# adc_AD7714.net
KiCad netlist of a schematic drawn in Altium Designer
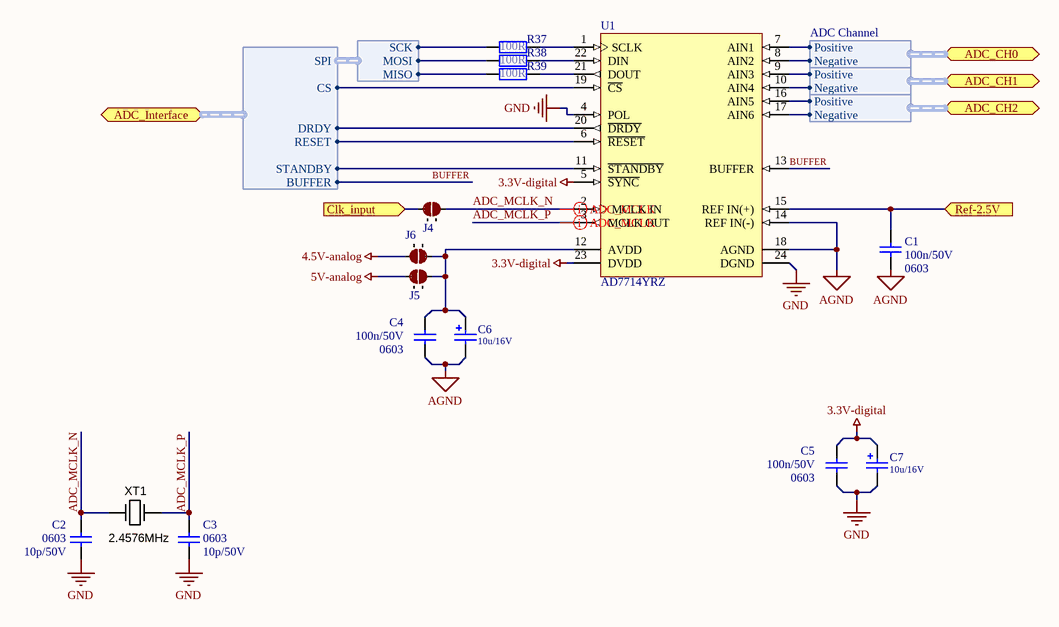
[diagram p0: adc_AD7714.SchDoc]

(export (version "E")
  (design (tool "Eeschema 10.0.6"))
  (components
    (comp (ref "C1")
      (value "100n/50V")
      (footprint "SMD_Capacitor_0603")
      (description "Ceramic Cap Kemet COTS 100n/50V X7R 0603")
      (fields
        (field (name "MANUFACTURER") "Kemet")
        (field (name "MANUFACTURERPARTNUMBER") "C0603T104K5RALTU")
        (field (name "PACKAGE") "0603")
      )
      (libsource (lib "capacitors") (part "Cer_C0603T104K5RALTU"))
    )
    (comp (ref "C2")
      (value "10p/50V")
      (footprint "SMD_Capacitor_0603")
      (description "Ceramic Cap Murata Automotive 10p/50V C0G 0603")
      (fields
        (field (name "MANUFACTURER") "Murata")
        (field (name "MANUFACTURERPARTNUMBER") "GCM1885C1H100JA16D")
        (field (name "PACKAGE") "0603")
      )
      (libsource (lib "capacitors") (part "Cer_GCM1885C1H100JA16D"))
    )
    (comp (ref "C3")
      (value "10p/50V")
      (footprint "SMD_Capacitor_0603")
      (description "Ceramic Cap Murata Automotive 10p/50V C0G 0603")
      (fields
        (field (name "MANUFACTURER") "Murata")
        (field (name "MANUFACTURERPARTNUMBER") "GCM1885C1H100JA16D")
        (field (name "PACKAGE") "0603")
      )
      (libsource (lib "capacitors") (part "Cer_GCM1885C1H100JA16D"))
    )
    (comp (ref "C4")
      (value "100n/50V")
      (footprint "SMD_Capacitor_0603")
      (description "Ceramic Cap Kemet COTS 100n/50V X7R 0603")
      (fields
        (field (name "MANUFACTURER") "Kemet")
        (field (name "MANUFACTURERPARTNUMBER") "C0603T104K5RALTU")
        (field (name "PACKAGE") "0603")
      )
      (libsource (lib "capacitors") (part "Cer_C0603T104K5RALTU"))
    )
    (comp (ref "C5")
      (value "100n/50V")
      (footprint "SMD_Capacitor_0603")
      (description "Ceramic Cap Kemet COTS 100n/50V X7R 0603")
      (fields
        (field (name "MANUFACTURER") "Kemet")
        (field (name "MANUFACTURERPARTNUMBER") "C0603T104K5RALTU")
        (field (name "PACKAGE") "0603")
      )
      (libsource (lib "capacitors") (part "Cer_C0603T104K5RALTU"))
    )
    (comp (ref "C6")
      (value "10u/16V")
      (footprint "Tantalum_cap_B")
      (description "Tantalum Capacitor")
      (libsource (lib "GG") (part "Cap Tantalum"))
    )
    (comp (ref "C7")
      (value "10u/16V")
      (footprint "Tantalum_cap_B")
      (description "Tantalum Capacitor")
      (libsource (lib "GG") (part "Cap Tantalum"))
    )
    (comp (ref "J4")
      (value "2 way net solder junction - Normally Open")
      (footprint "2waySolder_NO - 20 mils")
      (libsource (lib "NetTieLib") (part "2waySolderNO"))
    )
    (comp (ref "J5")
      (value "2 way net solder junction - Normally Open")
      (footprint "2waySolder_NO - 20 mils")
      (libsource (lib "NetTieLib") (part "2waySolderNO"))
    )
    (comp (ref "J6")
      (value "2 way net solder junction - Normally Open")
      (footprint "2waySolder_NO - 20 mils")
      (libsource (lib "NetTieLib") (part "2waySolderNO"))
    )
    (comp (ref "R37")
      (value "100R")
      (footprint "0603")
      (description "Generic resistor")
      (libsource (lib "GG") (part "Res"))
    )
    (comp (ref "R38")
      (value "100R")
      (footprint "0603")
      (description "Generic resistor")
      (libsource (lib "GG") (part "Res"))
    )
    (comp (ref "R39")
      (value "100R")
      (footprint "0603")
      (description "Generic resistor")
      (libsource (lib "GG") (part "Res"))
    )
    (comp (ref "U1")
      (value "AD7714YRZ")
      (footprint "RW-24_M")
      (fields (field (name "GENERIC PART NUMBER") "AD7714") (field (name "MANUFACTURER") "Analog Devices"))
      (libsource (lib "Analog Devices Data Converters Analog-to-Digital Converters") (part "AD7714YRZ"))
    )
    (comp (ref "XT1")
      (value "2.4576MHz")
      (footprint "HC49U")
      (description "AKER  C-2.4576-18-3050-X")
      (fields (field (name "TOLERANCE") "±50ppm"))
      (libsource (lib "crystal") (part "Crystal"))
    )
  )
  (nets
    (net (code "6") (name "/ADC_MCLK_N") (class "Default")
      (node (ref "C2") (pin "1") (pinfunction "1_1") (pintype "passive"))
      (node (ref "J4") (pin "2") (pinfunction "2_2") (pintype "passive"))
      (node (ref "U1") (pin "2") (pinfunction "MCLK_IN_2") (pintype "input"))
      (node (ref "XT1") (pin "1") (pinfunction "IN_1") (pintype "passive"))
    )
    (net (code "7") (name "/ADC_MCLK_P") (class "Default")
      (node (ref "C3") (pin "1") (pinfunction "1_1") (pintype "passive"))
      (node (ref "U1") (pin "3") (pinfunction "MCLK_OUT_3") (pintype "output"))
      (node (ref "XT1") (pin "2") (pinfunction "OUT_2") (pintype "passive"))
    )
    (net (code "8") (name "/BUFFER") (class "Default")
      (node (ref "U1") (pin "13") (pinfunction "BUFFER_13") (pintype "input"))
    )
    (net (code "9") (name "/CS") (class "Default")
      (node (ref "U1") (pin "19") (pinfunction "~{CS}_19") (pintype "input"))
    )
    (net (code "10") (name "/Clk_input") (class "Default")
      (node (ref "J4") (pin "1") (pinfunction "1_1") (pintype "passive"))
    )
    (net (code "11") (name "/DRDY") (class "Default")
      (node (ref "U1") (pin "20") (pinfunction "~{DRDY}_20") (pintype "output"))
    )
    (net (code "12") (name "/MISO") (class "Default")
      (node (ref "R39") (pin "1") (pinfunction "1_1") (pintype "passive"))
    )
    (net (code "13") (name "/MOSI") (class "Default")
      (node (ref "R38") (pin "1") (pinfunction "1_1") (pintype "passive"))
    )
    (net (code "14") (name "/RESET") (class "Default")
      (node (ref "U1") (pin "6") (pinfunction "~{RESET}_6") (pintype "input"))
    )
    (net (code "15") (name "/Ref-2.5V") (class "Default")
      (node (ref "C1") (pin "1") (pinfunction "1_1") (pintype "passive"))
      (node (ref "U1") (pin "15") (pinfunction "REF_IN(+)_15") (pintype "input"))
    )
    (net (code "16") (name "/SCK") (class "Default")
      (node (ref "R37") (pin "1") (pinfunction "1_1") (pintype "passive"))
    )
    (net (code "17") (name "/STANDBY") (class "Default")
      (node (ref "U1") (pin "11") (pinfunction "~{STANDBY}_11") (pintype "input"))
    )
    (net (code "20") (name "3.3V-digital") (class "Default")
      (node (ref "C5") (pin "1") (pinfunction "1_1") (pintype "passive"))
      (node (ref "C7") (pin "1") (pinfunction "1_1") (pintype "passive"))
      (node (ref "U1") (pin "23") (pinfunction "DVDD_23") (pintype "power_in"))
      (node (ref "U1") (pin "5") (pinfunction "~{SYNC}_5") (pintype "input"))
    )
    (net (code "21") (name "4.5V-analog") (class "Default")
      (node (ref "J6") (pin "2") (pinfunction "2_2") (pintype "passive"))
    )
    (net (code "22") (name "5V-analog") (class "Default")
      (node (ref "J5") (pin "1") (pinfunction "1_1") (pintype "passive"))
    )
    (net (code "23") (name "AGND") (class "Default")
      (node (ref "C1") (pin "2") (pinfunction "2_2") (pintype "passive"))
      (node (ref "C4") (pin "2") (pinfunction "2_2") (pintype "passive"))
      (node (ref "C6") (pin "2") (pinfunction "2_2") (pintype "passive"))
      (node (ref "U1") (pin "14") (pinfunction "REF_IN(-)_14") (pintype "input"))
      (node (ref "U1") (pin "18") (pinfunction "AGND_18") (pintype "power_in"))
    )
    (net (code "24") (name "GND") (class "Default")
      (node (ref "C2") (pin "2") (pinfunction "2_2") (pintype "passive"))
      (node (ref "C3") (pin "2") (pinfunction "2_2") (pintype "passive"))
      (node (ref "C5") (pin "2") (pinfunction "2_2") (pintype "passive"))
      (node (ref "C7") (pin "2") (pinfunction "2_2") (pintype "passive"))
      (node (ref "U1") (pin "24") (pinfunction "DGND_24") (pintype "power_in"))
      (node (ref "U1") (pin "4") (pinfunction "POL_4") (pintype "input"))
    )
    (net (code "25") (name "Net-(U1-AVDD)") (class "Default")
      (node (ref "C4") (pin "1") (pinfunction "1_1") (pintype "passive"))
      (node (ref "C6") (pin "1") (pinfunction "1_1") (pintype "passive"))
      (node (ref "J5") (pin "2") (pinfunction "2_2") (pintype "passive"))
      (node (ref "J6") (pin "1") (pinfunction "1_1") (pintype "passive"))
      (node (ref "U1") (pin "12") (pinfunction "AVDD_12") (pintype "power_in"))
    )
    (net (code "26") (name "Net-(U1-DIN)") (class "Default")
      (node (ref "R38") (pin "2") (pinfunction "2_2") (pintype "passive"))
      (node (ref "U1") (pin "22") (pinfunction "DIN_22") (pintype "input"))
    )
    (net (code "27") (name "Net-(U1-DOUT)") (class "Default")
      (node (ref "R39") (pin "2") (pinfunction "2_2") (pintype "passive"))
      (node (ref "U1") (pin "21") (pinfunction "DOUT_21") (pintype "output"))
    )
    (net (code "28") (name "Net-(U1-SCLK)") (class "Default")
      (node (ref "R37") (pin "2") (pinfunction "2_2") (pintype "passive"))
      (node (ref "U1") (pin "1") (pinfunction "SCLK_1") (pintype "input"))
    )
    (net (code "29") (name "unconnected-(U1-AIN1-Pad7)") (class "Default")
      (node (ref "U1") (pin "7") (pinfunction "AIN1_7") (pintype "input"))
    )
    (net (code "30") (name "unconnected-(U1-AIN2-Pad8)") (class "Default")
      (node (ref "U1") (pin "8") (pinfunction "AIN2_8") (pintype "input"))
    )
    (net (code "31") (name "unconnected-(U1-AIN3-Pad9)") (class "Default")
      (node (ref "U1") (pin "9") (pinfunction "AIN3_9") (pintype "input"))
    )
    (net (code "32") (name "unconnected-(U1-AIN4-Pad10)") (class "Default")
      (node (ref "U1") (pin "10") (pinfunction "AIN4_10") (pintype "input"))
    )
    (net (code "33") (name "unconnected-(U1-AIN5-Pad16)") (class "Default")
      (node (ref "U1") (pin "16") (pinfunction "AIN5_16") (pintype "input"))
    )
    (net (code "34") (name "unconnected-(U1-AIN6-Pad17)") (class "Default")
      (node (ref "U1") (pin "17") (pinfunction "AIN6_17") (pintype "input"))
    )
  )
)
